# isl2.net
KiCad netlist of a schematic drawn in EAGLE
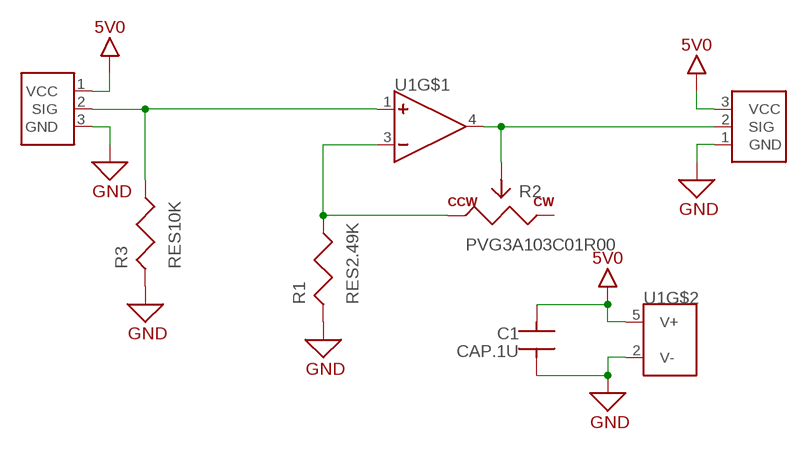
[diagram p0: schematic, sheet 1]

(export (version "E")
  (design (tool "Eeschema 10.0.6"))
  (components
    (comp (ref "C1")
      (value "CAP.1U")
      (footprint "eagle-import:SMT0603")
      (fields (field (name "MFR") "Murata") (field (name "MPN") "GRM188R71H104KA93D"))
      (libsource (lib "eagle-import") (part "CAP.1U"))
    )
    (comp (ref "J1")
      (value "BITSNAPINPUT")
      (footprint "eagle-import:BITSNAP_INPUT_MALE")
      (libsource (lib "eagle-import") (part "BITSNAPINPUT"))
    )
    (comp (ref "J2")
      (value "BITSNAPOUTPUT")
      (footprint "eagle-import:BITSNAP_OUTPUT_FEMALE")
      (libsource (lib "eagle-import") (part "BITSNAPOUTPUT"))
    )
    (comp (ref "R1")
      (value "RES2.49K")
      (footprint "eagle-import:SMT0603")
      (libsource (lib "eagle-import") (part "RES2.49K"))
    )
    (comp (ref "R2")
      (value "PVG3A103C01R00")
      (footprint "eagle-import:PVG3A")
      (libsource (lib "eagle-import") (part "PVG3A103C01R00"))
    )
    (comp (ref "R3")
      (value "RES10K")
      (footprint "eagle-import:SMT0603")
      (fields (field (name "MFR") "Panasonic") (field (name "MPN") "ERJ-3EKF1002V "))
      (libsource (lib "eagle-import") (part "RES10K"))
    )
    (comp (ref "U1")
      (value "LMV321")
      (footprint "eagle-import:SOT23-5")
      (libsource (lib "eagle-import") (part "LMV321"))
    )
  )
  (nets
    (net (code "1") (name "5V0") (class "Default")
      (node (ref "C1") (pin "2") (pinfunction "2_2") (pintype "bidirectional"))
      (node (ref "J1") (pin "1") (pinfunction "VCC_1") (pintype "bidirectional"))
      (node (ref "J2") (pin "3") (pinfunction "VCC_3") (pintype "bidirectional"))
      (node (ref "U1") (pin "5") (pinfunction "V+_5") (pintype "bidirectional"))
    )
    (net (code "2") (name "GND") (class "Default")
      (node (ref "C1") (pin "1") (pinfunction "1_1") (pintype "bidirectional"))
      (node (ref "J1") (pin "3") (pinfunction "GND_3") (pintype "bidirectional"))
      (node (ref "J2") (pin "1") (pinfunction "GND_1") (pintype "bidirectional"))
      (node (ref "R1") (pin "1") (pinfunction "1_1") (pintype "bidirectional"))
      (node (ref "R3") (pin "1") (pinfunction "1_1") (pintype "bidirectional"))
      (node (ref "U1") (pin "2") (pinfunction "V-_2") (pintype "bidirectional"))
    )
    (net (code "3") (name "Net-(J1-SIG)") (class "Default")
      (node (ref "J1") (pin "2") (pinfunction "SIG_2") (pintype "bidirectional"))
      (node (ref "R3") (pin "2") (pinfunction "2_2") (pintype "bidirectional"))
      (node (ref "U1") (pin "1") (pinfunction "IN+_1") (pintype "bidirectional"))
    )
    (net (code "4") (name "Net-(J2-SIG)") (class "Default")
      (node (ref "J2") (pin "2") (pinfunction "SIG_2") (pintype "bidirectional"))
      (node (ref "R2") (pin "2") (pinfunction "WIPER_2") (pintype "bidirectional"))
      (node (ref "U1") (pin "4") (pinfunction "OUT_4") (pintype "bidirectional"))
    )
    (net (code "5") (name "Net-(R2-CCW)") (class "Default")
      (node (ref "R1") (pin "2") (pinfunction "2_2") (pintype "bidirectional"))
      (node (ref "R2") (pin "1") (pinfunction "CCW_1") (pintype "bidirectional"))
      (node (ref "U1") (pin "3") (pinfunction "IN-_3") (pintype "bidirectional"))
    )
    (net (code "6") (name "unconnected-(R2-CW-Pad3)") (class "Default")
      (node (ref "R2") (pin "3") (pinfunction "CW_3") (pintype "bidirectional"))
    )
  )
)
